# Sheet1.net
KiCad netlist of a schematic drawn in Altium Designer
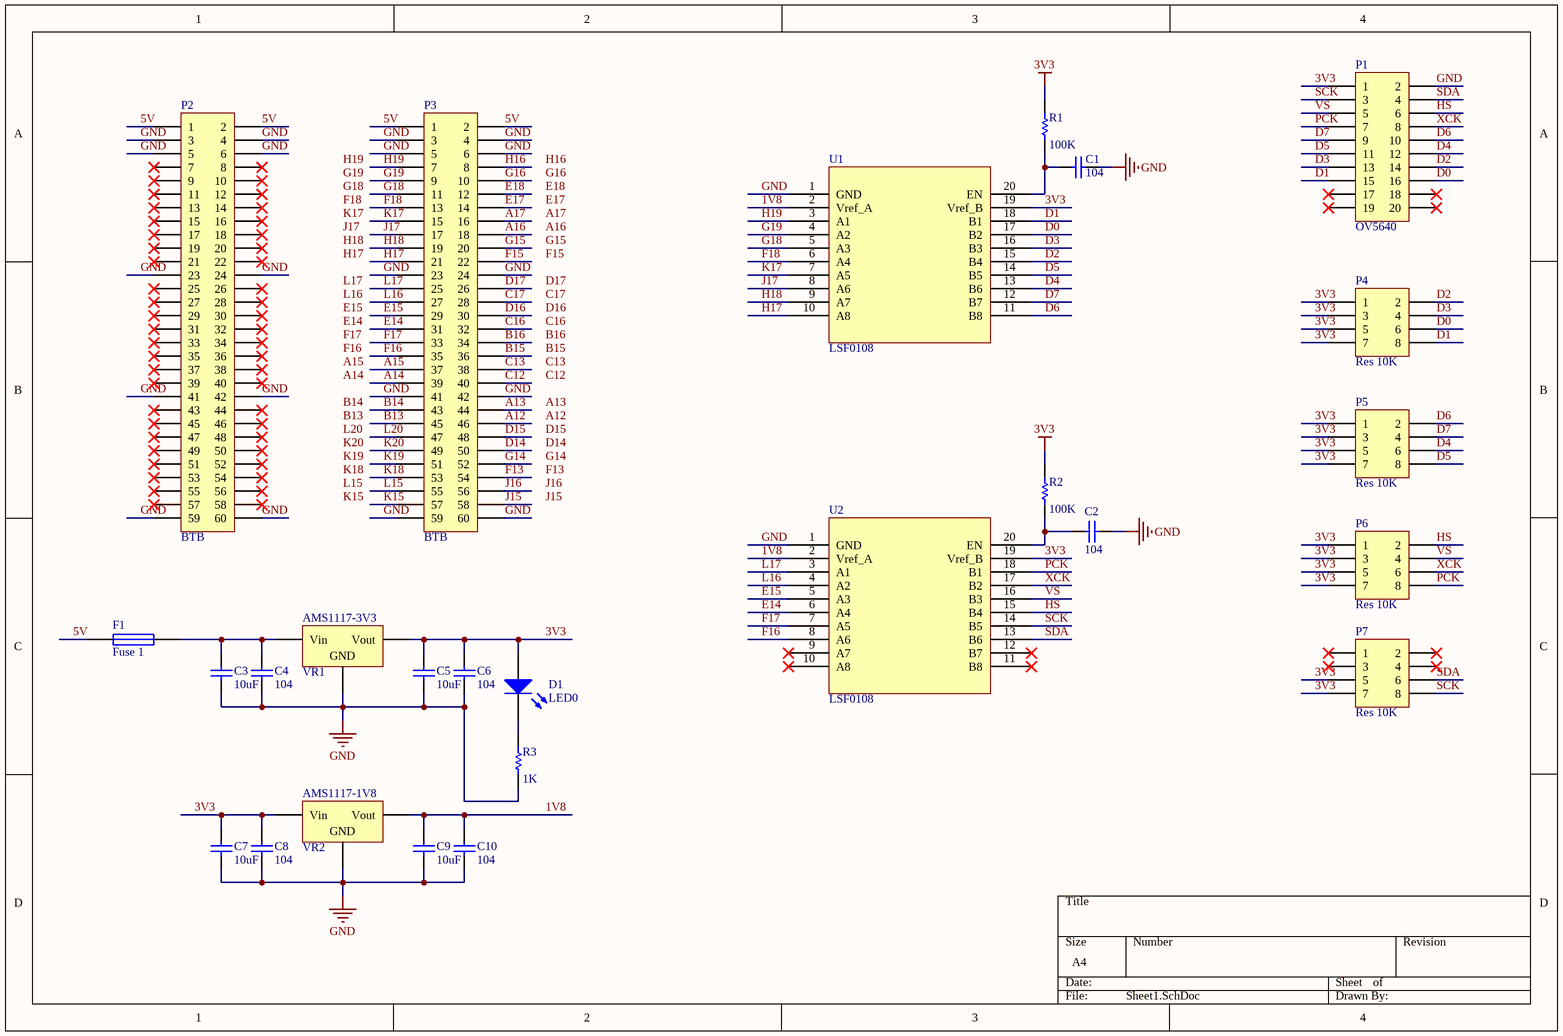
[diagram p0: Sheet1.SchDoc]

(export (version "E")
  (design (tool "Eeschema 10.0.6"))
  (components
    (comp (ref "C1")
      (value "104")
      (footprint "R0805")
      (description "Capacitor")
      (fields (field (name "Comment") "Cap") (field (name "PUBLISHER") "Altium Limited"))
      (libsource (lib "Miscellaneous Devices") (part "Cap"))
    )
    (comp (ref "C2")
      (value "104")
      (footprint "R0805")
      (description "Capacitor")
      (fields (field (name "Comment") "Cap") (field (name "PUBLISHER") "Altium Limited"))
      (libsource (lib "Miscellaneous Devices") (part "Cap"))
    )
    (comp (ref "C3")
      (value "10uF")
      (footprint "R0805")
      (description "Capacitor")
      (fields (field (name "Comment") "Cap") (field (name "PUBLISHER") "Altium Limited"))
      (libsource (lib "Miscellaneous Devices") (part "Cap"))
    )
    (comp (ref "C4")
      (value "104")
      (footprint "R0805")
      (description "Capacitor")
      (fields (field (name "Comment") "Cap") (field (name "PUBLISHER") "Altium Limited"))
      (libsource (lib "Miscellaneous Devices") (part "Cap"))
    )
    (comp (ref "C5")
      (value "10uF")
      (footprint "R0805")
      (description "Capacitor")
      (fields (field (name "Comment") "Cap") (field (name "PUBLISHER") "Altium Limited"))
      (libsource (lib "Miscellaneous Devices") (part "Cap"))
    )
    (comp (ref "C6")
      (value "104")
      (footprint "R0805")
      (description "Capacitor")
      (fields (field (name "Comment") "Cap") (field (name "PUBLISHER") "Altium Limited"))
      (libsource (lib "Miscellaneous Devices") (part "Cap"))
    )
    (comp (ref "C7")
      (value "10uF")
      (footprint "R0805")
      (description "Capacitor")
      (fields (field (name "Comment") "Cap") (field (name "PUBLISHER") "Altium Limited"))
      (libsource (lib "Miscellaneous Devices") (part "Cap"))
    )
    (comp (ref "C8")
      (value "104")
      (footprint "R0805")
      (description "Capacitor")
      (fields (field (name "Comment") "Cap") (field (name "PUBLISHER") "Altium Limited"))
      (libsource (lib "Miscellaneous Devices") (part "Cap"))
    )
    (comp (ref "C9")
      (value "10uF")
      (footprint "R0805")
      (description "Capacitor")
      (fields (field (name "Comment") "Cap") (field (name "PUBLISHER") "Altium Limited"))
      (libsource (lib "Miscellaneous Devices") (part "Cap"))
    )
    (comp (ref "C10")
      (value "104")
      (footprint "R0805")
      (description "Capacitor")
      (fields (field (name "Comment") "Cap") (field (name "PUBLISHER") "Altium Limited"))
      (libsource (lib "Miscellaneous Devices") (part "Cap"))
    )
    (comp (ref "D1")
      (value "LED0")
      (footprint "LED0805红")
      (description "Typical INFRARED GaAs LED")
      (fields (field (name "PUBLISHER") "Altium Limited"))
      (libsource (lib "Miscellaneous Devices") (part "LED0"))
    )
    (comp (ref "F1")
      (value "Fuse 1")
      (footprint "R0805")
      (description "Fuse")
      (fields (field (name "PUBLISHER") "Altium Limited"))
      (libsource (lib "Miscellaneous Devices") (part "Fuse 1"))
    )
    (comp (ref "P1")
      (value "OV5640")
      (footprint "HDR2X10")
      (description "Header, 10-Pin, Dual row")
      (fields (field (name "PUBLISHER") "Altium Limited"))
      (libsource (lib "Miscellaneous Connectors") (part "Header 10X2"))
    )
    (comp (ref "P2")
      (value "BTB")
      (footprint "BTBCON_0.8mm_60P")
      (description "Header, 30-Pin, Dual row")
      (fields (field (name "PUBLISHER") "Altium Limited"))
      (libsource (lib "Miscellaneous Connectors") (part "Header 30X2"))
    )
    (comp (ref "P3")
      (value "BTB")
      (footprint "BTBCON_0.8mm_60P")
      (description "Header, 30-Pin, Dual row")
      (fields (field (name "PUBLISHER") "Altium Limited"))
      (libsource (lib "Miscellaneous Connectors") (part "Header 30X2"))
    )
    (comp (ref "P4")
      (value "Res 10K")
      (footprint "排阻(4位贴片)")
      (description "Header, 4-Pin, Dual row")
      (fields (field (name "PUBLISHER") "Altium Limited"))
      (libsource (lib "Miscellaneous Connectors") (part "Header 4X2"))
    )
    (comp (ref "P5")
      (value "Res 10K")
      (footprint "排阻(4位贴片)")
      (description "Header, 4-Pin, Dual row")
      (fields (field (name "PUBLISHER") "Altium Limited"))
      (libsource (lib "Miscellaneous Connectors") (part "Header 4X2"))
    )
    (comp (ref "P6")
      (value "Res 10K")
      (footprint "排阻(4位贴片)")
      (description "Header, 4-Pin, Dual row")
      (fields (field (name "PUBLISHER") "Altium Limited"))
      (libsource (lib "Miscellaneous Connectors") (part "Header 4X2"))
    )
    (comp (ref "P7")
      (value "Res 10K")
      (footprint "排阻(4位贴片)")
      (description "Header, 4-Pin, Dual row")
      (fields (field (name "PUBLISHER") "Altium Limited"))
      (libsource (lib "Miscellaneous Connectors") (part "Header 4X2"))
    )
    (comp (ref "R1")
      (value "100K")
      (footprint "R0805")
      (description "Semiconductor Resistor")
      (fields (field (name "Comment") "Res Semi") (field (name "PUBLISHER") "Altium Limited"))
      (libsource (lib "Miscellaneous Devices") (part "Res Semi"))
    )
    (comp (ref "R2")
      (value "100K")
      (footprint "R0805")
      (description "Semiconductor Resistor")
      (fields (field (name "Comment") "Res Semi") (field (name "PUBLISHER") "Altium Limited"))
      (libsource (lib "Miscellaneous Devices") (part "Res Semi"))
    )
    (comp (ref "R3")
      (value "1K")
      (footprint "R0805")
      (description "Resistor")
      (fields (field (name "Comment") "Res1") (field (name "PUBLISHER") "Altium Limited"))
      (libsource (lib "Miscellaneous Devices") (part "Res1"))
    )
    (comp (ref "U1")
      (value "LSF0108")
      (footprint "TSSOP20 74lvc245")
      (libsource (lib "LSF0108") (part "LSF0108"))
    )
    (comp (ref "U2")
      (value "LSF0108")
      (footprint "TSSOP20 74lvc245")
      (libsource (lib "LSF0108") (part "LSF0108"))
    )
    (comp (ref "VR1")
      (value "AMS1117-3V3")
      (footprint "SOT-223")
      (description "Voltage Regulator")
      (fields (field (name "PUBLISHER") "Altium Limited"))
      (libsource (lib "Miscellaneous Devices") (part "Volt Reg"))
    )
    (comp (ref "VR2")
      (value "AMS1117-1V8")
      (footprint "SOT-223")
      (description "Voltage Regulator")
      (fields (field (name "PUBLISHER") "Altium Limited"))
      (libsource (lib "Miscellaneous Devices") (part "Volt Reg"))
    )
  )
  (nets
    (net (code "1") (name "/1V8") (class "Default")
      (node (ref "C10") (pin "2") (pinfunction "2_2") (pintype "passive"))
      (node (ref "C9") (pin "2") (pinfunction "2_2") (pintype "passive"))
      (node (ref "U1") (pin "2") (pinfunction "Vref_A_2") (pintype "passive"))
      (node (ref "U2") (pin "2") (pinfunction "Vref_A_2") (pintype "passive"))
      (node (ref "VR2") (pin "2") (pinfunction "Vout_2") (pintype "passive"))
    )
    (net (code "2") (name "/5V") (class "Default")
      (node (ref "F1") (pin "1") (pinfunction "1_1") (pintype "passive"))
      (node (ref "P2") (pin "1") (pinfunction "1_1") (pintype "passive"))
      (node (ref "P2") (pin "2") (pinfunction "2_2") (pintype "passive"))
      (node (ref "P3") (pin "1") (pinfunction "1_1") (pintype "passive"))
      (node (ref "P3") (pin "2") (pinfunction "2_2") (pintype "passive"))
    )
    (net (code "3") (name "/A12") (class "Default")
      (node (ref "P3") (pin "46") (pinfunction "46_46") (pintype "passive"))
    )
    (net (code "4") (name "/A13") (class "Default")
      (node (ref "P3") (pin "44") (pinfunction "44_44") (pintype "passive"))
    )
    (net (code "5") (name "/A14") (class "Default")
      (node (ref "P3") (pin "39") (pinfunction "39_39") (pintype "passive"))
    )
    (net (code "6") (name "/A15") (class "Default")
      (node (ref "P3") (pin "37") (pinfunction "37_37") (pintype "passive"))
    )
    (net (code "7") (name "/A16") (class "Default")
      (node (ref "P3") (pin "18") (pinfunction "18_18") (pintype "passive"))
    )
    (net (code "8") (name "/A17") (class "Default")
      (node (ref "P3") (pin "16") (pinfunction "16_16") (pintype "passive"))
    )
    (net (code "9") (name "/B13") (class "Default")
      (node (ref "P3") (pin "45") (pinfunction "45_45") (pintype "passive"))
    )
    (net (code "10") (name "/B14") (class "Default")
      (node (ref "P3") (pin "43") (pinfunction "43_43") (pintype "passive"))
    )
    (net (code "11") (name "/B15") (class "Default")
      (node (ref "P3") (pin "36") (pinfunction "36_36") (pintype "passive"))
    )
    (net (code "12") (name "/B16") (class "Default")
      (node (ref "P3") (pin "34") (pinfunction "34_34") (pintype "passive"))
    )
    (net (code "13") (name "/C12") (class "Default")
      (node (ref "P3") (pin "40") (pinfunction "40_40") (pintype "passive"))
    )
    (net (code "14") (name "/C13") (class "Default")
      (node (ref "P3") (pin "38") (pinfunction "38_38") (pintype "passive"))
    )
    (net (code "15") (name "/C16") (class "Default")
      (node (ref "P3") (pin "32") (pinfunction "32_32") (pintype "passive"))
    )
    (net (code "16") (name "/C17") (class "Default")
      (node (ref "P3") (pin "28") (pinfunction "28_28") (pintype "passive"))
    )
    (net (code "17") (name "/D0") (class "Default")
      (node (ref "P1") (pin "16") (pinfunction "16_16") (pintype "passive"))
      (node (ref "P4") (pin "6") (pinfunction "6_6") (pintype "passive"))
      (node (ref "U1") (pin "17") (pinfunction "B2_17") (pintype "passive"))
    )
    (net (code "18") (name "/D1") (class "Default")
      (node (ref "P1") (pin "15") (pinfunction "15_15") (pintype "passive"))
      (node (ref "P4") (pin "8") (pinfunction "8_8") (pintype "passive"))
      (node (ref "U1") (pin "18") (pinfunction "B1_18") (pintype "passive"))
    )
    (net (code "19") (name "/D2") (class "Default")
      (node (ref "P1") (pin "14") (pinfunction "14_14") (pintype "passive"))
      (node (ref "P4") (pin "2") (pinfunction "2_2") (pintype "passive"))
      (node (ref "U1") (pin "15") (pinfunction "B4_15") (pintype "passive"))
    )
    (net (code "20") (name "/D3") (class "Default")
      (node (ref "P1") (pin "13") (pinfunction "13_13") (pintype "passive"))
      (node (ref "P4") (pin "4") (pinfunction "4_4") (pintype "passive"))
      (node (ref "U1") (pin "16") (pinfunction "B3_16") (pintype "passive"))
    )
    (net (code "21") (name "/D4") (class "Default")
      (node (ref "P1") (pin "12") (pinfunction "12_12") (pintype "passive"))
      (node (ref "P5") (pin "6") (pinfunction "6_6") (pintype "passive"))
      (node (ref "U1") (pin "13") (pinfunction "B6_13") (pintype "passive"))
    )
    (net (code "22") (name "/D5") (class "Default")
      (node (ref "P1") (pin "11") (pinfunction "11_11") (pintype "passive"))
      (node (ref "P5") (pin "8") (pinfunction "8_8") (pintype "passive"))
      (node (ref "U1") (pin "14") (pinfunction "B5_14") (pintype "passive"))
    )
    (net (code "23") (name "/D6") (class "Default")
      (node (ref "P1") (pin "10") (pinfunction "10_10") (pintype "passive"))
      (node (ref "P5") (pin "2") (pinfunction "2_2") (pintype "passive"))
      (node (ref "U1") (pin "11") (pinfunction "B8_11") (pintype "passive"))
    )
    (net (code "24") (name "/D7") (class "Default")
      (node (ref "P1") (pin "9") (pinfunction "9_9") (pintype "passive"))
      (node (ref "P5") (pin "4") (pinfunction "4_4") (pintype "passive"))
      (node (ref "U1") (pin "12") (pinfunction "B7_12") (pintype "passive"))
    )
    (net (code "25") (name "/D14") (class "Default")
      (node (ref "P3") (pin "50") (pinfunction "50_50") (pintype "passive"))
    )
    (net (code "26") (name "/D15") (class "Default")
      (node (ref "P3") (pin "48") (pinfunction "48_48") (pintype "passive"))
    )
    (net (code "27") (name "/D16") (class "Default")
      (node (ref "P3") (pin "30") (pinfunction "30_30") (pintype "passive"))
    )
    (net (code "28") (name "/D17") (class "Default")
      (node (ref "P3") (pin "26") (pinfunction "26_26") (pintype "passive"))
    )
    (net (code "29") (name "/E14") (class "Default")
      (node (ref "P3") (pin "31") (pinfunction "31_31") (pintype "passive"))
      (node (ref "U2") (pin "6") (pinfunction "A4_6") (pintype "passive"))
    )
    (net (code "30") (name "/E15") (class "Default")
      (node (ref "P3") (pin "29") (pinfunction "29_29") (pintype "passive"))
      (node (ref "U2") (pin "5") (pinfunction "A3_5") (pintype "passive"))
    )
    (net (code "31") (name "/E17") (class "Default")
      (node (ref "P3") (pin "14") (pinfunction "14_14") (pintype "passive"))
    )
    (net (code "32") (name "/E18") (class "Default")
      (node (ref "P3") (pin "12") (pinfunction "12_12") (pintype "passive"))
    )
    (net (code "33") (name "/F13") (class "Default")
      (node (ref "P3") (pin "54") (pinfunction "54_54") (pintype "passive"))
    )
    (net (code "34") (name "/F15") (class "Default")
      (node (ref "P3") (pin "22") (pinfunction "22_22") (pintype "passive"))
    )
    (net (code "35") (name "/F16") (class "Default")
      (node (ref "P3") (pin "35") (pinfunction "35_35") (pintype "passive"))
      (node (ref "U2") (pin "8") (pinfunction "A6_8") (pintype "passive"))
    )
    (net (code "36") (name "/F17") (class "Default")
      (node (ref "P3") (pin "33") (pinfunction "33_33") (pintype "passive"))
      (node (ref "U2") (pin "7") (pinfunction "A5_7") (pintype "passive"))
    )
    (net (code "37") (name "/F18") (class "Default")
      (node (ref "P3") (pin "13") (pinfunction "13_13") (pintype "passive"))
      (node (ref "U1") (pin "6") (pinfunction "A4_6") (pintype "passive"))
    )
    (net (code "38") (name "/G14") (class "Default")
      (node (ref "P3") (pin "52") (pinfunction "52_52") (pintype "passive"))
    )
    (net (code "39") (name "/G15") (class "Default")
      (node (ref "P3") (pin "20") (pinfunction "20_20") (pintype "passive"))
    )
    (net (code "40") (name "/G16") (class "Default")
      (node (ref "P3") (pin "10") (pinfunction "10_10") (pintype "passive"))
    )
    (net (code "41") (name "/G18") (class "Default")
      (node (ref "P3") (pin "11") (pinfunction "11_11") (pintype "passive"))
      (node (ref "U1") (pin "5") (pinfunction "A3_5") (pintype "passive"))
    )
    (net (code "42") (name "/G19") (class "Default")
      (node (ref "P3") (pin "9") (pinfunction "9_9") (pintype "passive"))
      (node (ref "U1") (pin "4") (pinfunction "A2_4") (pintype "passive"))
    )
    (net (code "43") (name "/H16") (class "Default")
      (node (ref "P3") (pin "8") (pinfunction "8_8") (pintype "passive"))
    )
    (net (code "44") (name "/H17") (class "Default")
      (node (ref "P3") (pin "21") (pinfunction "21_21") (pintype "passive"))
      (node (ref "U1") (pin "10") (pinfunction "A8_10") (pintype "passive"))
    )
    (net (code "45") (name "/H18") (class "Default")
      (node (ref "P3") (pin "19") (pinfunction "19_19") (pintype "passive"))
      (node (ref "U1") (pin "9") (pinfunction "A7_9") (pintype "passive"))
    )
    (net (code "46") (name "/H19") (class "Default")
      (node (ref "P3") (pin "7") (pinfunction "7_7") (pintype "passive"))
      (node (ref "U1") (pin "3") (pinfunction "A1_3") (pintype "passive"))
    )
    (net (code "47") (name "/HS") (class "Default")
      (node (ref "P1") (pin "6") (pinfunction "6_6") (pintype "passive"))
      (node (ref "P6") (pin "2") (pinfunction "2_2") (pintype "passive"))
      (node (ref "U2") (pin "15") (pinfunction "B4_15") (pintype "passive"))
    )
    (net (code "48") (name "/J15") (class "Default")
      (node (ref "P3") (pin "58") (pinfunction "58_58") (pintype "passive"))
    )
    (net (code "49") (name "/J16") (class "Default")
      (node (ref "P3") (pin "56") (pinfunction "56_56") (pintype "passive"))
    )
    (net (code "50") (name "/J17") (class "Default")
      (node (ref "P3") (pin "17") (pinfunction "17_17") (pintype "passive"))
      (node (ref "U1") (pin "8") (pinfunction "A6_8") (pintype "passive"))
    )
    (net (code "51") (name "/K15") (class "Default")
      (node (ref "P3") (pin "57") (pinfunction "57_57") (pintype "passive"))
    )
    (net (code "52") (name "/K17") (class "Default")
      (node (ref "P3") (pin "15") (pinfunction "15_15") (pintype "passive"))
      (node (ref "U1") (pin "7") (pinfunction "A5_7") (pintype "passive"))
    )
    (net (code "53") (name "/K18") (class "Default")
      (node (ref "P3") (pin "53") (pinfunction "53_53") (pintype "passive"))
    )
    (net (code "54") (name "/K19") (class "Default")
      (node (ref "P3") (pin "51") (pinfunction "51_51") (pintype "passive"))
    )
    (net (code "55") (name "/K20") (class "Default")
      (node (ref "P3") (pin "49") (pinfunction "49_49") (pintype "passive"))
    )
    (net (code "56") (name "/L15") (class "Default")
      (node (ref "P3") (pin "55") (pinfunction "55_55") (pintype "passive"))
    )
    (net (code "57") (name "/L16") (class "Default")
      (node (ref "P3") (pin "27") (pinfunction "27_27") (pintype "passive"))
      (node (ref "U2") (pin "4") (pinfunction "A2_4") (pintype "passive"))
    )
    (net (code "58") (name "/L17") (class "Default")
      (node (ref "P3") (pin "25") (pinfunction "25_25") (pintype "passive"))
      (node (ref "U2") (pin "3") (pinfunction "A1_3") (pintype "passive"))
    )
    (net (code "59") (name "/L20") (class "Default")
      (node (ref "P3") (pin "47") (pinfunction "47_47") (pintype "passive"))
    )
    (net (code "60") (name "/PCK") (class "Default")
      (node (ref "P1") (pin "7") (pinfunction "7_7") (pintype "passive"))
      (node (ref "P6") (pin "8") (pinfunction "8_8") (pintype "passive"))
      (node (ref "U2") (pin "18") (pinfunction "B1_18") (pintype "passive"))
    )
    (net (code "61") (name "/SCK") (class "Default")
      (node (ref "P1") (pin "3") (pinfunction "3_3") (pintype "passive"))
      (node (ref "P7") (pin "8") (pinfunction "8_8") (pintype "passive"))
      (node (ref "U2") (pin "14") (pinfunction "B5_14") (pintype "passive"))
    )
    (net (code "62") (name "/SDA") (class "Default")
      (node (ref "P1") (pin "4") (pinfunction "4_4") (pintype "passive"))
      (node (ref "P7") (pin "6") (pinfunction "6_6") (pintype "passive"))
      (node (ref "U2") (pin "13") (pinfunction "B6_13") (pintype "passive"))
    )
    (net (code "63") (name "/VS") (class "Default")
      (node (ref "P1") (pin "5") (pinfunction "5_5") (pintype "passive"))
      (node (ref "P6") (pin "4") (pinfunction "4_4") (pintype "passive"))
      (node (ref "U2") (pin "16") (pinfunction "B3_16") (pintype "passive"))
    )
    (net (code "64") (name "/XCK") (class "Default")
      (node (ref "P1") (pin "8") (pinfunction "8_8") (pintype "passive"))
      (node (ref "P6") (pin "6") (pinfunction "6_6") (pintype "passive"))
      (node (ref "U2") (pin "17") (pinfunction "B2_17") (pintype "passive"))
    )
    (net (code "65") (name "3V3") (class "Default")
      (node (ref "C5") (pin "2") (pinfunction "2_2") (pintype "passive"))
      (node (ref "C6") (pin "2") (pinfunction "2_2") (pintype "passive"))
      (node (ref "C7") (pin "2") (pinfunction "2_2") (pintype "passive"))
      (node (ref "C8") (pin "2") (pinfunction "2_2") (pintype "passive"))
      (node (ref "D1") (pin "1") (pinfunction "A_1") (pintype "passive"))
      (node (ref "P1") (pin "1") (pinfunction "1_1") (pintype "passive"))
      (node (ref "P4") (pin "1") (pinfunction "1_1") (pintype "passive"))
      (node (ref "P4") (pin "3") (pinfunction "3_3") (pintype "passive"))
      (node (ref "P4") (pin "5") (pinfunction "5_5") (pintype "passive"))
      (node (ref "P4") (pin "7") (pinfunction "7_7") (pintype "passive"))
      (node (ref "P5") (pin "1") (pinfunction "1_1") (pintype "passive"))
      (node (ref "P5") (pin "3") (pinfunction "3_3") (pintype "passive"))
      (node (ref "P5") (pin "5") (pinfunction "5_5") (pintype "passive"))
      (node (ref "P5") (pin "7") (pinfunction "7_7") (pintype "passive"))
      (node (ref "P6") (pin "1") (pinfunction "1_1") (pintype "passive"))
      (node (ref "P6") (pin "3") (pinfunction "3_3") (pintype "passive"))
      (node (ref "P6") (pin "5") (pinfunction "5_5") (pintype "passive"))
      (node (ref "P6") (pin "7") (pinfunction "7_7") (pintype "passive"))
      (node (ref "P7") (pin "5") (pinfunction "5_5") (pintype "passive"))
      (node (ref "P7") (pin "7") (pinfunction "7_7") (pintype "passive"))
      (node (ref "R1") (pin "2") (pinfunction "2_2") (pintype "passive"))
      (node (ref "R2") (pin "2") (pinfunction "2_2") (pintype "passive"))
      (node (ref "U1") (pin "19") (pinfunction "Vref_B_19") (pintype "passive"))
      (node (ref "U2") (pin "19") (pinfunction "Vref_B_19") (pintype "passive"))
      (node (ref "VR1") (pin "2") (pinfunction "Vout_2") (pintype "passive"))
      (node (ref "VR2") (pin "3") (pinfunction "Vin_3") (pintype "passive"))
    )
    (net (code "66") (name "GND") (class "Default")
      (node (ref "C1") (pin "2") (pinfunction "2_2") (pintype "passive"))
      (node (ref "C10") (pin "1") (pinfunction "1_1") (pintype "passive"))
      (node (ref "C2") (pin "1") (pinfunction "1_1") (pintype "passive"))
      (node (ref "C3") (pin "1") (pinfunction "1_1") (pintype "passive"))
      (node (ref "C4") (pin "1") (pinfunction "1_1") (pintype "passive"))
      (node (ref "C5") (pin "1") (pinfunction "1_1") (pintype "passive"))
      (node (ref "C6") (pin "1") (pinfunction "1_1") (pintype "passive"))
      (node (ref "C7") (pin "1") (pinfunction "1_1") (pintype "passive"))
      (node (ref "C8") (pin "1") (pinfunction "1_1") (pintype "passive"))
      (node (ref "C9") (pin "1") (pinfunction "1_1") (pintype "passive"))
      (node (ref "P1") (pin "2") (pinfunction "2_2") (pintype "passive"))
      (node (ref "P2") (pin "23") (pinfunction "23_23") (pintype "passive"))
      (node (ref "P2") (pin "24") (pinfunction "24_24") (pintype "passive"))
      (node (ref "P2") (pin "3") (pinfunction "3_3") (pintype "passive"))
      (node (ref "P2") (pin "4") (pinfunction "4_4") (pintype "passive"))
      (node (ref "P2") (pin "41") (pinfunction "41_41") (pintype "passive"))
      (node (ref "P2") (pin "42") (pinfunction "42_42") (pintype "passive"))
      (node (ref "P2") (pin "5") (pinfunction "5_5") (pintype "passive"))
      (node (ref "P2") (pin "59") (pinfunction "59_59") (pintype "passive"))
      (node (ref "P2") (pin "6") (pinfunction "6_6") (pintype "passive"))
      (node (ref "P2") (pin "60") (pinfunction "60_60") (pintype "passive"))
      (node (ref "P3") (pin "23") (pinfunction "23_23") (pintype "passive"))
      (node (ref "P3") (pin "24") (pinfunction "24_24") (pintype "passive"))
      (node (ref "P3") (pin "3") (pinfunction "3_3") (pintype "passive"))
      (node (ref "P3") (pin "4") (pinfunction "4_4") (pintype "passive"))
      (node (ref "P3") (pin "41") (pinfunction "41_41") (pintype "passive"))
      (node (ref "P3") (pin "42") (pinfunction "42_42") (pintype "passive"))
      (node (ref "P3") (pin "5") (pinfunction "5_5") (pintype "passive"))
      (node (ref "P3") (pin "59") (pinfunction "59_59") (pintype "passive"))
      (node (ref "P3") (pin "6") (pinfunction "6_6") (pintype "passive"))
      (node (ref "P3") (pin "60") (pinfunction "60_60") (pintype "passive"))
      (node (ref "R3") (pin "1") (pinfunction "1_1") (pintype "passive"))
      (node (ref "U1") (pin "1") (pinfunction "GND_1") (pintype "passive"))
      (node (ref "U2") (pin "1") (pinfunction "GND_1") (pintype "passive"))
      (node (ref "VR1") (pin "1") (pinfunction "GND_1") (pintype "passive"))
      (node (ref "VR2") (pin "1") (pinfunction "GND_1") (pintype "passive"))
    )
    (net (code "67") (name "Net-(D1-K)") (class "Default")
      (node (ref "D1") (pin "2") (pinfunction "K_2") (pintype "passive"))
      (node (ref "R3") (pin "2") (pinfunction "2_2") (pintype "passive"))
    )
    (net (code "68") (name "Net-(U1-EN)") (class "Default")
      (node (ref "C1") (pin "1") (pinfunction "1_1") (pintype "passive"))
      (node (ref "R1") (pin "1") (pinfunction "1_1") (pintype "passive"))
      (node (ref "U1") (pin "20") (pinfunction "EN_20") (pintype "passive"))
    )
    (net (code "69") (name "Net-(U2-EN)") (class "Default")
      (node (ref "C2") (pin "2") (pinfunction "2_2") (pintype "passive"))
      (node (ref "R2") (pin "1") (pinfunction "1_1") (pintype "passive"))
      (node (ref "U2") (pin "20") (pinfunction "EN_20") (pintype "passive"))
    )
    (net (code "70") (name "Net-(VR1-Vin)") (class "Default")
      (node (ref "C3") (pin "2") (pinfunction "2_2") (pintype "passive"))
      (node (ref "C4") (pin "2") (pinfunction "2_2") (pintype "passive"))
      (node (ref "F1") (pin "2") (pinfunction "2_2") (pintype "passive"))
      (node (ref "VR1") (pin "3") (pinfunction "Vin_3") (pintype "passive"))
    )
    (net (code "71") (name "unconnected-(P1-Pad17)") (class "Default")
      (node (ref "P1") (pin "17") (pinfunction "17_17") (pintype "passive+no_connect"))
    )
    (net (code "72") (name "unconnected-(P1-Pad18)") (class "Default")
      (node (ref "P1") (pin "18") (pinfunction "18_18") (pintype "passive+no_connect"))
    )
    (net (code "73") (name "unconnected-(P1-Pad19)") (class "Default")
      (node (ref "P1") (pin "19") (pinfunction "19_19") (pintype "passive+no_connect"))
    )
    (net (code "74") (name "unconnected-(P1-Pad20)") (class "Default")
      (node (ref "P1") (pin "20") (pinfunction "20_20") (pintype "passive+no_connect"))
    )
    (net (code "75") (name "unconnected-(P2-Pad7)") (class "Default")
      (node (ref "P2") (pin "7") (pinfunction "7_7") (pintype "passive+no_connect"))
    )
    (net (code "76") (name "unconnected-(P2-Pad8)") (class "Default")
      (node (ref "P2") (pin "8") (pinfunction "8_8") (pintype "passive+no_connect"))
    )
    (net (code "77") (name "unconnected-(P2-Pad9)") (class "Default")
      (node (ref "P2") (pin "9") (pinfunction "9_9") (pintype "passive+no_connect"))
    )
    (net (code "78") (name "unconnected-(P2-Pad10)") (class "Default")
      (node (ref "P2") (pin "10") (pinfunction "10_10") (pintype "passive+no_connect"))
    )
    (net (code "79") (name "unconnected-(P2-Pad11)") (class "Default")
      (node (ref "P2") (pin "11") (pinfunction "11_11") (pintype "passive+no_connect"))
    )
    (net (code "80") (name "unconnected-(P2-Pad12)") (class "Default")
      (node (ref "P2") (pin "12") (pinfunction "12_12") (pintype "passive+no_connect"))
    )
    (net (code "81") (name "unconnected-(P2-Pad13)") (class "Default")
      (node (ref "P2") (pin "13") (pinfunction "13_13") (pintype "passive+no_connect"))
    )
    (net (code "82") (name "unconnected-(P2-Pad14)") (class "Default")
      (node (ref "P2") (pin "14") (pinfunction "14_14") (pintype "passive+no_connect"))
    )
    (net (code "83") (name "unconnected-(P2-Pad15)") (class "Default")
      (node (ref "P2") (pin "15") (pinfunction "15_15") (pintype "passive+no_connect"))
    )
    (net (code "84") (name "unconnected-(P2-Pad16)") (class "Default")
      (node (ref "P2") (pin "16") (pinfunction "16_16") (pintype "passive+no_connect"))
    )
    (net (code "85") (name "unconnected-(P2-Pad17)") (class "Default")
      (node (ref "P2") (pin "17") (pinfunction "17_17") (pintype "passive+no_connect"))
    )
    (net (code "86") (name "unconnected-(P2-Pad18)") (class "Default")
      (node (ref "P2") (pin "18") (pinfunction "18_18") (pintype "passive+no_connect"))
    )
    (net (code "87") (name "unconnected-(P2-Pad19)") (class "Default")
      (node (ref "P2") (pin "19") (pinfunction "19_19") (pintype "passive+no_connect"))
    )
    (net (code "88") (name "unconnected-(P2-Pad20)") (class "Default")
      (node (ref "P2") (pin "20") (pinfunction "20_20") (pintype "passive+no_connect"))
    )
    (net (code "89") (name "unconnected-(P2-Pad21)") (class "Default")
      (node (ref "P2") (pin "21") (pinfunction "21_21") (pintype "passive+no_connect"))
    )
    (net (code "90") (name "unconnected-(P2-Pad22)") (class "Default")
      (node (ref "P2") (pin "22") (pinfunction "22_22") (pintype "passive+no_connect"))
    )
    (net (code "91") (name "unconnected-(P2-Pad25)") (class "Default")
      (node (ref "P2") (pin "25") (pinfunction "25_25") (pintype "passive+no_connect"))
    )
    (net (code "92") (name "unconnected-(P2-Pad26)") (class "Default")
      (node (ref "P2") (pin "26") (pinfunction "26_26") (pintype "passive+no_connect"))
    )
    (net (code "93") (name "unconnected-(P2-Pad27)") (class "Default")
      (node (ref "P2") (pin "27") (pinfunction "27_27") (pintype "passive+no_connect"))
    )
    (net (code "94") (name "unconnected-(P2-Pad28)") (class "Default")
      (node (ref "P2") (pin "28") (pinfunction "28_28") (pintype "passive+no_connect"))
    )
    (net (code "95") (name "unconnected-(P2-Pad29)") (class "Default")
      (node (ref "P2") (pin "29") (pinfunction "29_29") (pintype "passive+no_connect"))
    )
    (net (code "96") (name "unconnected-(P2-Pad30)") (class "Default")
      (node (ref "P2") (pin "30") (pinfunction "30_30") (pintype "passive+no_connect"))
    )
    (net (code "97") (name "unconnected-(P2-Pad31)") (class "Default")
      (node (ref "P2") (pin "31") (pinfunction "31_31") (pintype "passive+no_connect"))
    )
    (net (code "98") (name "unconnected-(P2-Pad32)") (class "Default")
      (node (ref "P2") (pin "32") (pinfunction "32_32") (pintype "passive+no_connect"))
    )
    (net (code "99") (name "unconnected-(P2-Pad33)") (class "Default")
      (node (ref "P2") (pin "33") (pinfunction "33_33") (pintype "passive+no_connect"))
    )
    (net (code "100") (name "unconnected-(P2-Pad34)") (class "Default")
      (node (ref "P2") (pin "34") (pinfunction "34_34") (pintype "passive+no_connect"))
    )
    (net (code "101") (name "unconnected-(P2-Pad35)") (class "Default")
      (node (ref "P2") (pin "35") (pinfunction "35_35") (pintype "passive+no_connect"))
    )
    (net (code "102") (name "unconnected-(P2-Pad36)") (class "Default")
      (node (ref "P2") (pin "36") (pinfunction "36_36") (pintype "passive+no_connect"))
    )
    (net (code "103") (name "unconnected-(P2-Pad37)") (class "Default")
      (node (ref "P2") (pin "37") (pinfunction "37_37") (pintype "passive+no_connect"))
    )
    (net (code "104") (name "unconnected-(P2-Pad38)") (class "Default")
      (node (ref "P2") (pin "38") (pinfunction "38_38") (pintype "passive+no_connect"))
    )
    (net (code "105") (name "unconnected-(P2-Pad39)") (class "Default")
      (node (ref "P2") (pin "39") (pinfunction "39_39") (pintype "passive+no_connect"))
    )
    (net (code "106") (name "unconnected-(P2-Pad40)") (class "Default")
      (node (ref "P2") (pin "40") (pinfunction "40_40") (pintype "passive+no_connect"))
    )
    (net (code "107") (name "unconnected-(P2-Pad43)") (class "Default")
      (node (ref "P2") (pin "43") (pinfunction "43_43") (pintype "passive+no_connect"))
    )
    (net (code "108") (name "unconnected-(P2-Pad44)") (class "Default")
      (node (ref "P2") (pin "44") (pinfunction "44_44") (pintype "passive+no_connect"))
    )
    (net (code "109") (name "unconnected-(P2-Pad45)") (class "Default")
      (node (ref "P2") (pin "45") (pinfunction "45_45") (pintype "passive+no_connect"))
    )
    (net (code "110") (name "unconnected-(P2-Pad46)") (class "Default")
      (node (ref "P2") (pin "46") (pinfunction "46_46") (pintype "passive+no_connect"))
    )
    (net (code "111") (name "unconnected-(P2-Pad47)") (class "Default")
      (node (ref "P2") (pin "47") (pinfunction "47_47") (pintype "passive+no_connect"))
    )
    (net (code "112") (name "unconnected-(P2-Pad48)") (class "Default")
      (node (ref "P2") (pin "48") (pinfunction "48_48") (pintype "passive+no_connect"))
    )
    (net (code "113") (name "unconnected-(P2-Pad49)") (class "Default")
      (node (ref "P2") (pin "49") (pinfunction "49_49") (pintype "passive+no_connect"))
    )
    (net (code "114") (name "unconnected-(P2-Pad50)") (class "Default")
      (node (ref "P2") (pin "50") (pinfunction "50_50") (pintype "passive+no_connect"))
    )
    (net (code "115") (name "unconnected-(P2-Pad51)") (class "Default")
      (node (ref "P2") (pin "51") (pinfunction "51_51") (pintype "passive+no_connect"))
    )
    (net (code "116") (name "unconnected-(P2-Pad52)") (class "Default")
      (node (ref "P2") (pin "52") (pinfunction "52_52") (pintype "passive+no_connect"))
    )
    (net (code "117") (name "unconnected-(P2-Pad53)") (class "Default")
      (node (ref "P2") (pin "53") (pinfunction "53_53") (pintype "passive+no_connect"))
    )
    (net (code "118") (name "unconnected-(P2-Pad54)") (class "Default")
      (node (ref "P2") (pin "54") (pinfunction "54_54") (pintype "passive+no_connect"))
    )
    (net (code "119") (name "unconnected-(P2-Pad55)") (class "Default")
      (node (ref "P2") (pin "55") (pinfunction "55_55") (pintype "passive+no_connect"))
    )
    (net (code "120") (name "unconnected-(P2-Pad56)") (class "Default")
      (node (ref "P2") (pin "56") (pinfunction "56_56") (pintype "passive+no_connect"))
    )
    (net (code "121") (name "unconnected-(P2-Pad57)") (class "Default")
      (node (ref "P2") (pin "57") (pinfunction "57_57") (pintype "passive+no_connect"))
    )
    (net (code "122") (name "unconnected-(P2-Pad58)") (class "Default")
      (node (ref "P2") (pin "58") (pinfunction "58_58") (pintype "passive+no_connect"))
    )
    (net (code "123") (name "unconnected-(P7-Pad1)") (class "Default")
      (node (ref "P7") (pin "1") (pinfunction "1_1") (pintype "passive+no_connect"))
    )
    (net (code "124") (name "unconnected-(P7-Pad2)") (class "Default")
      (node (ref "P7") (pin "2") (pinfunction "2_2") (pintype "passive+no_connect"))
    )
    (net (code "125") (name "unconnected-(P7-Pad3)") (class "Default")
      (node (ref "P7") (pin "3") (pinfunction "3_3") (pintype "passive+no_connect"))
    )
    (net (code "126") (name "unconnected-(P7-Pad4)") (class "Default")
      (node (ref "P7") (pin "4") (pinfunction "4_4") (pintype "passive+no_connect"))
    )
    (net (code "127") (name "unconnected-(U2-A7-Pad9)") (class "Default")
      (node (ref "U2") (pin "9") (pinfunction "A7_9") (pintype "passive+no_connect"))
    )
    (net (code "128") (name "unconnected-(U2-A8-Pad10)") (class "Default")
      (node (ref "U2") (pin "10") (pinfunction "A8_10") (pintype "passive+no_connect"))
    )
    (net (code "129") (name "unconnected-(U2-B7-Pad12)") (class "Default")
      (node (ref "U2") (pin "12") (pinfunction "B7_12") (pintype "passive+no_connect"))
    )
    (net (code "130") (name "unconnected-(U2-B8-Pad11)") (class "Default")
      (node (ref "U2") (pin "11") (pinfunction "B8_11") (pintype "passive+no_connect"))
    )
  )
)
